# d_00_e_02.net
KiCad netlist of a schematic drawn in EasyEDA
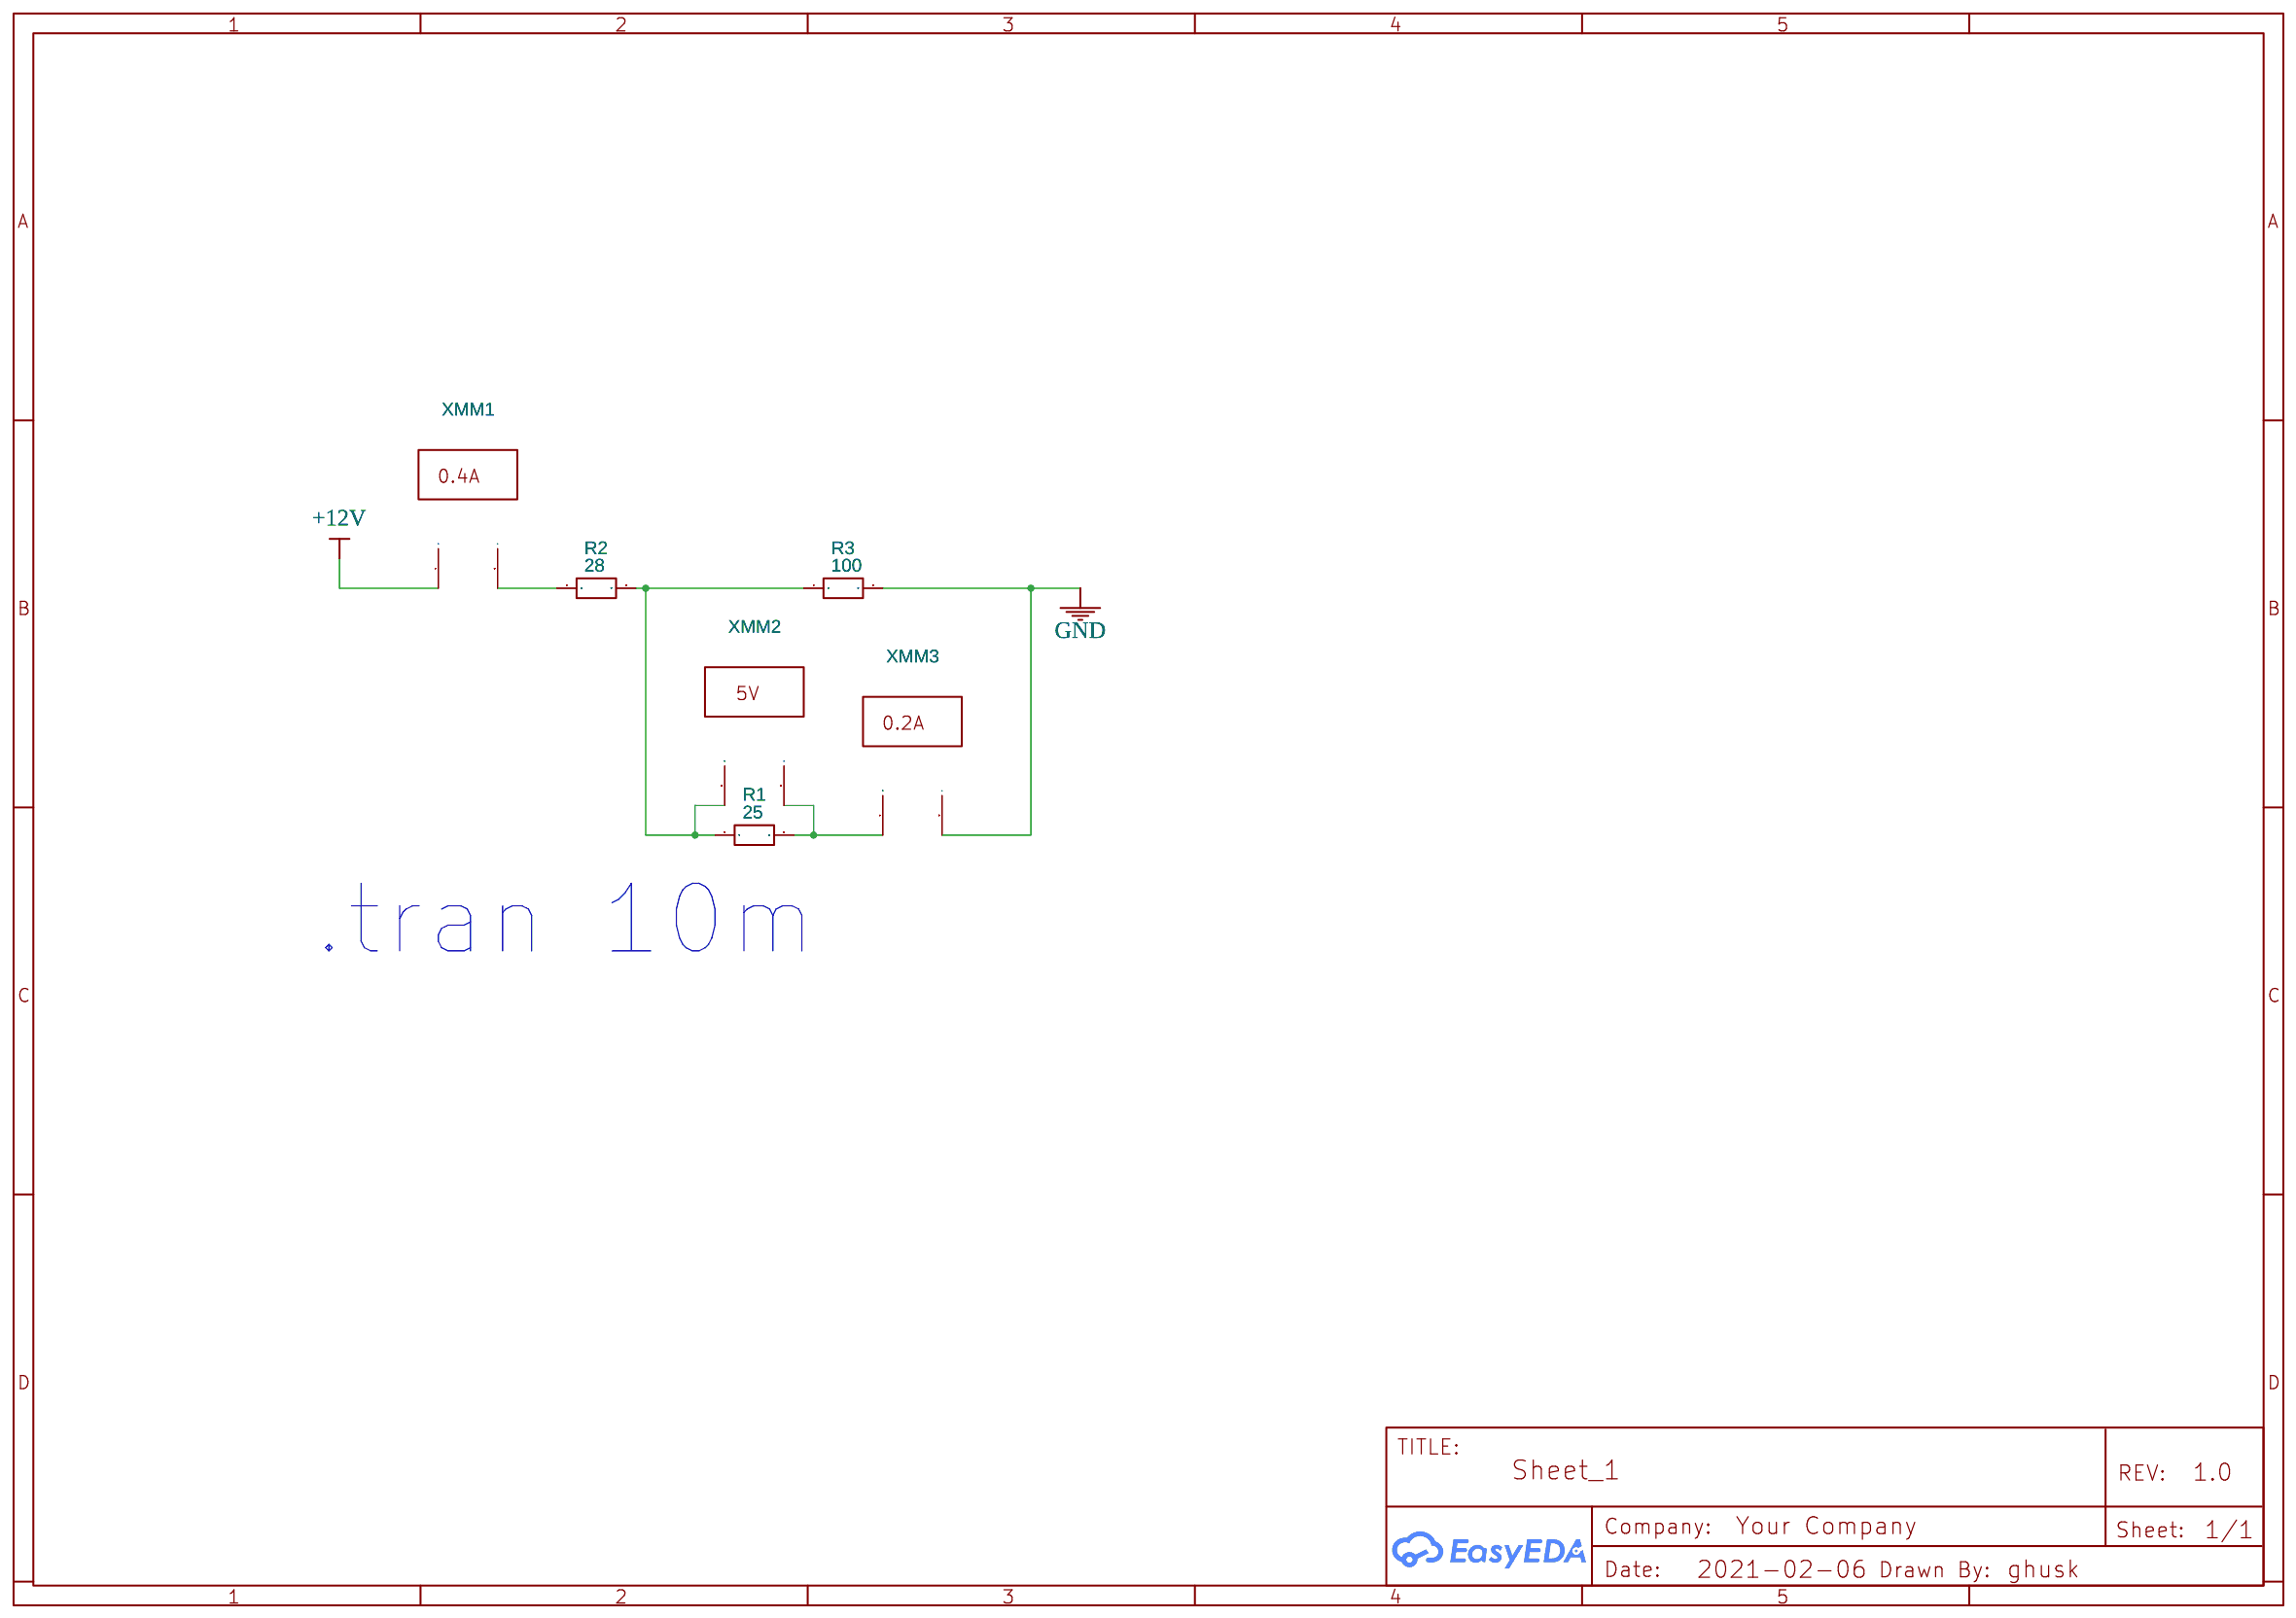
[diagram p0: schematic sheet]

(export (version "E")
  (design (tool "Eeschema 10.0.6"))
  (components
    (comp (ref "R1") (value "25") (libsource (lib "") (part "Resistor_EU")))
    (comp (ref "R2") (value "28") (libsource (lib "") (part "Resistor_EU")))
    (comp (ref "R3") (value "100") (libsource (lib "") (part "Resistor_EU")))
    (comp (ref "XMM1") (value "Multimeter") (libsource (lib "") (part "MULTIMETER_2")))
    (comp (ref "XMM2") (value "Multimeter") (libsource (lib "") (part "MULTIMETER_1")))
    (comp (ref "XMM3") (value "Multimeter") (libsource (lib "") (part "MULTIMETER")))
  )
  (nets
    (net (code "1") (name "+12V") (class "Default")
      (node (ref "XMM1") (pin "1") (pinfunction "+_1") (pintype "unspecified"))
    )
    (net (code "2") (name "GND") (class "Default")
      (node (ref "R3") (pin "2") (pinfunction "2_2") (pintype "unspecified"))
      (node (ref "XMM3") (pin "2") (pinfunction "I_2") (pintype "unspecified"))
    )
    (net (code "3") (name "Net-(XMM1-I)") (class "Default")
      (node (ref "R2") (pin "1") (pinfunction "1_1") (pintype "unspecified"))
      (node (ref "XMM1") (pin "2") (pinfunction "I_2") (pintype "unspecified"))
    )
    (net (code "4") (name "Net-(XMM2-+)") (class "Default")
      (node (ref "R1") (pin "1") (pinfunction "1_1") (pintype "unspecified"))
      (node (ref "R2") (pin "2") (pinfunction "2_2") (pintype "unspecified"))
      (node (ref "R3") (pin "1") (pinfunction "1_1") (pintype "unspecified"))
      (node (ref "XMM2") (pin "1") (pinfunction "+_1") (pintype "unspecified"))
    )
    (net (code "5") (name "Net-(XMM2-I)") (class "Default")
      (node (ref "R1") (pin "2") (pinfunction "2_2") (pintype "unspecified"))
      (node (ref "XMM2") (pin "2") (pinfunction "I_2") (pintype "unspecified"))
      (node (ref "XMM3") (pin "1") (pinfunction "+_1") (pintype "unspecified"))
    )
  )
)
